# climate_control.net
KiCad netlist of a schematic drawn in EAGLE
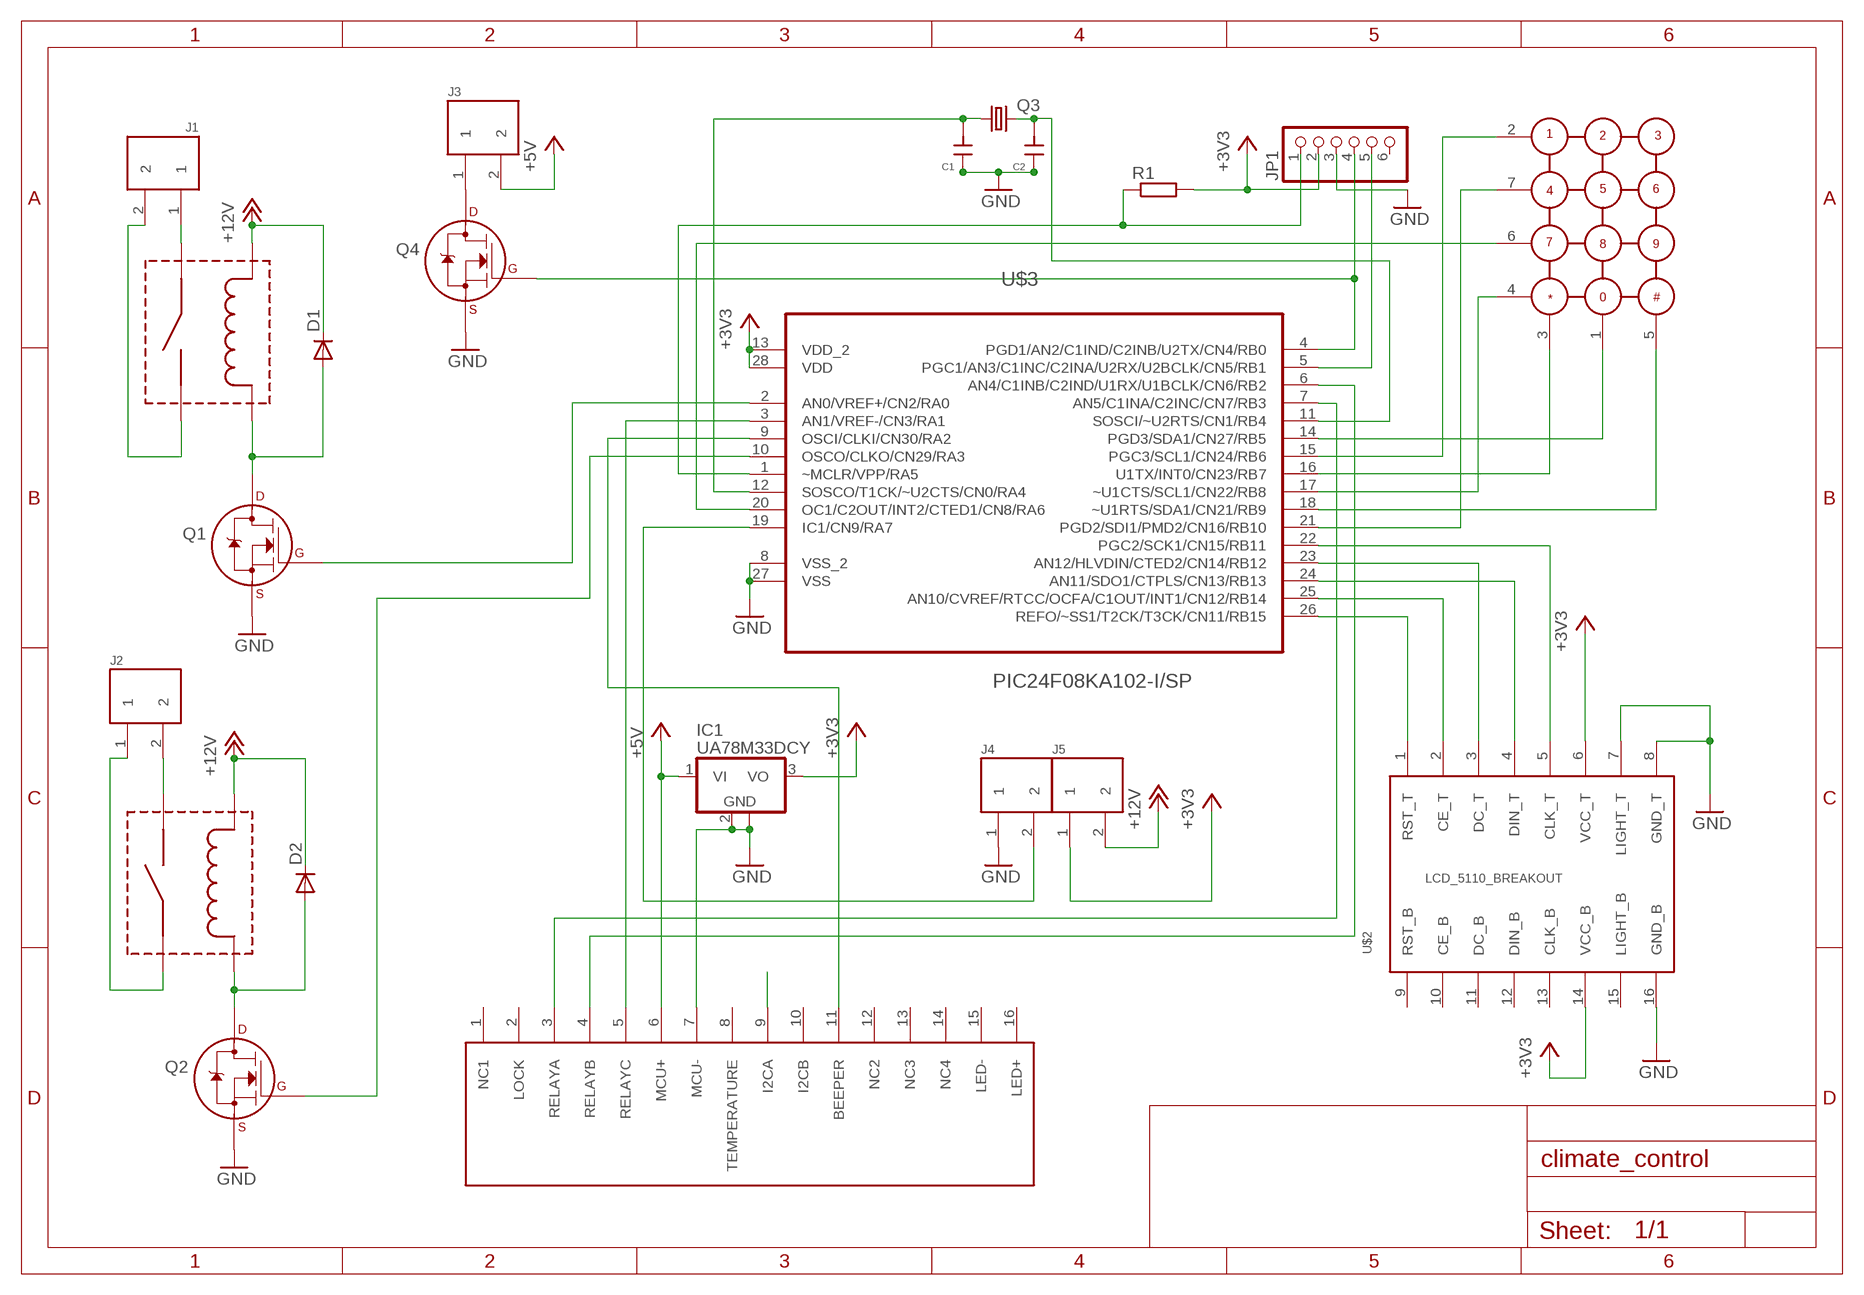
[diagram p0: schematic, sheet 1]

(export (version "E")
  (design (tool "Eeschema 10.0.6"))
  (components
    (comp (ref "C1")
      (value "DUALCAP")
      (footprint "eagle-import:DUALCAP")
      (libsource (lib "eagle-import") (part "DUALCAP"))
    )
    (comp (ref "C2")
      (value "DUALCAP")
      (footprint "eagle-import:DUALCAP")
      (libsource (lib "eagle-import") (part "DUALCAP"))
    )
    (comp (ref "D1")
      (value "DIODE-DO-214AC")
      (footprint "eagle-import:DO-214AC")
      (libsource (lib "eagle-import") (part "DIODE-DO-214AC"))
    )
    (comp (ref "D2")
      (value "DIODE-DO-214AC")
      (footprint "eagle-import:DO-214AC")
      (libsource (lib "eagle-import") (part "DIODE-DO-214AC"))
    )
    (comp (ref "IC1")
      (value "UA78M33DCY")
      (footprint "eagle-import:SOT223")
      (libsource (lib "eagle-import") (part "UA78MDCY33"))
    )
    (comp (ref "J1")
      (value "TERMINAL_PCB_508_X2")
      (footprint "eagle-import:TERMINAL_PCB_508_PITCH")
      (libsource (lib "eagle-import") (part "TERMINAL_PCB_508_X2"))
    )
    (comp (ref "J2")
      (value "TERMINAL_PCB_508_X2")
      (footprint "eagle-import:TERMINAL_PCB_508_PITCH")
      (libsource (lib "eagle-import") (part "TERMINAL_PCB_508_X2"))
    )
    (comp (ref "J3")
      (value "TERMINAL_PCB_508_X2")
      (footprint "eagle-import:TERMINAL_PCB_508_PITCH")
      (libsource (lib "eagle-import") (part "TERMINAL_PCB_508_X2"))
    )
    (comp (ref "J4")
      (value "TERMINAL_PCB_508_X2")
      (footprint "eagle-import:TERMINAL_PCB_508_PITCH")
      (libsource (lib "eagle-import") (part "TERMINAL_PCB_508_X2"))
    )
    (comp (ref "J5")
      (value "TERMINAL_PCB_508_X2")
      (footprint "eagle-import:TERMINAL_PCB_508_PITCH")
      (libsource (lib "eagle-import") (part "TERMINAL_PCB_508_X2"))
    )
    (comp (ref "JP1")
      (value "PINHD-1X6")
      (footprint "eagle-import:1X06")
      (libsource (lib "eagle-import") (part "PINHD-1X6"))
    )
    (comp (ref "Q1")
      (value "2N7000_TO92")
      (footprint "eagle-import:TO-92")
      (libsource (lib "eagle-import") (part "2N700_TO920"))
    )
    (comp (ref "Q2")
      (value "2N7000_TO92")
      (footprint "eagle-import:TO-92")
      (libsource (lib "eagle-import") (part "2N700_TO920"))
    )
    (comp (ref "Q3")
      (value "CRYSTALTC38H")
      (footprint "eagle-import:TC38H")
      (libsource (lib "eagle-import") (part "CRYSTALTC38H"))
    )
    (comp (ref "Q4")
      (value "2N7000_TO92")
      (footprint "eagle-import:TO-92")
      (libsource (lib "eagle-import") (part "2N700_TO920"))
    )
    (comp (ref "R1")
      (value "R-EU_0207/10")
      (footprint "eagle-import:0207_10")
      (libsource (lib "eagle-import") (part "R-EU_0207/10"))
    )
    (comp (ref "U$1")
      (value "KEYPAD12")
      (footprint "eagle-import:KEYPAD12")
      (libsource (lib "eagle-import") (part "KEYPAD12"))
    )
    (comp (ref "U$2")
      (value "LCD_5110_BREAKOUT")
      (footprint "eagle-import:LCD_5110_BREAKOUT")
      (libsource (lib "eagle-import") (part "LCD_5110_BREAKOUT"))
    )
    (comp (ref "U$3")
      (value "PIC24F08KA102-I/SP")
      (footprint "eagle-import:DIP254P762X533-28")
      (fields (field (name "MPN") "PIC24F08kA102-I/SP"))
      (libsource (lib "eagle-import") (part "PIC24F08KA102-I/SP"))
    )
    (comp (ref "U$4")
      (value "WILLHI_EDGE")
      (footprint "eagle-import:WILLHI_EDGE")
      (libsource (lib "eagle-import") (part "WILLHI_EDGE"))
    )
    (comp (ref "U$5")
      (value "RELAY_JZC-33F")
      (footprint "eagle-import:RELAY_JZC-33F")
      (libsource (lib "eagle-import") (part "RELAY_JZC-33F"))
    )
    (comp (ref "U$7")
      (value "RELAY_JZC-33F")
      (footprint "eagle-import:RELAY_JZC-33F")
      (libsource (lib "eagle-import") (part "RELAY_JZC-33F"))
    )
  )
  (nets
    (net (code "1") (name "+3V3") (class "Default")
      (node (ref "IC1") (pin "3") (pinfunction "VO_3") (pintype "passive"))
      (node (ref "J5") (pin "1") (pinfunction "1_1") (pintype "bidirectional"))
      (node (ref "JP1") (pin "2") (pinfunction "2_2") (pintype "passive"))
      (node (ref "R1") (pin "2") (pinfunction "2_2") (pintype "passive"))
      (node (ref "U$2") (pin "14") (pinfunction "VCC_B_14") (pintype "power_in"))
      (node (ref "U$2") (pin "6") (pinfunction "VCC_T_6") (pintype "power_in"))
      (node (ref "U$3") (pin "13") (pinfunction "VDD_2_13") (pintype "passive"))
      (node (ref "U$3") (pin "28") (pinfunction "VDD_28") (pintype "power_in"))
    )
    (net (code "2") (name "+5V") (class "Default")
      (node (ref "IC1") (pin "1") (pinfunction "VI_1") (pintype "input"))
      (node (ref "J3") (pin "2") (pinfunction "2_2") (pintype "bidirectional"))
      (node (ref "U$4") (pin "6") (pinfunction "MCU+_6") (pintype "bidirectional"))
    )
    (net (code "3") (name "+12V") (class "Default")
      (node (ref "D1") (pin "C") (pinfunction "C_C") (pintype "passive"))
      (node (ref "D2") (pin "C") (pinfunction "C_C") (pintype "passive"))
      (node (ref "J5") (pin "2") (pinfunction "2_2") (pintype "bidirectional"))
      (node (ref "U$5") (pin "COIL1") (pinfunction "COIL1_COIL1") (pintype "passive"))
      (node (ref "U$7") (pin "COIL2") (pinfunction "COIL2_COIL2") (pintype "passive"))
    )
    (net (code "4") (name "GND") (class "Default")
      (node (ref "C1") (pin "P$2") (pinfunction "P$2_P$2") (pintype "passive"))
      (node (ref "C1") (pin "P$3") (pinfunction "P$1_P$3") (pintype "passive"))
      (node (ref "C2") (pin "P$2") (pinfunction "P$2_P$2") (pintype "passive"))
      (node (ref "C2") (pin "P$3") (pinfunction "P$1_P$3") (pintype "passive"))
      (node (ref "IC1") (pin "2") (pinfunction "GND_2") (pintype "passive"))
      (node (ref "IC1") (pin "4") (pinfunction "GND_4") (pintype "passive"))
      (node (ref "J4") (pin "1") (pinfunction "1_1") (pintype "bidirectional"))
      (node (ref "JP1") (pin "3") (pinfunction "3_3") (pintype "passive"))
      (node (ref "Q1") (pin "1") (pinfunction "S_1") (pintype "bidirectional"))
      (node (ref "Q2") (pin "1") (pinfunction "S_1") (pintype "bidirectional"))
      (node (ref "Q4") (pin "1") (pinfunction "S_1") (pintype "bidirectional"))
      (node (ref "U$2") (pin "16") (pinfunction "GND_B_16") (pintype "power_in"))
      (node (ref "U$2") (pin "7") (pinfunction "LIGHT_T_7") (pintype "input"))
      (node (ref "U$2") (pin "8") (pinfunction "GND_T_8") (pintype "power_in"))
      (node (ref "U$3") (pin "27") (pinfunction "VSS_27") (pintype "passive"))
      (node (ref "U$3") (pin "8") (pinfunction "VSS_2_8") (pintype "passive"))
      (node (ref "U$4") (pin "7") (pinfunction "MCU-_7") (pintype "bidirectional"))
    )
    (net (code "5") (name "Net-(C1-P$3)") (class "Default")
      (node (ref "C1") (pin "P$1") (pinfunction "P$3_P$1") (pintype "passive"))
      (node (ref "Q3") (pin "1") (pinfunction "1_1") (pintype "passive"))
      (node (ref "U$3") (pin "12") (pinfunction "SOSCO/T1CK/~{U2CTS/CN0/RA4}_12") (pintype "bidirectional"))
    )
    (net (code "6") (name "Net-(C2-P$3)") (class "Default")
      (node (ref "C2") (pin "P$1") (pinfunction "P$3_P$1") (pintype "passive"))
      (node (ref "Q3") (pin "2") (pinfunction "2_2") (pintype "passive"))
      (node (ref "U$3") (pin "11") (pinfunction "SOSCI/~{U2RTS/CN1/RB4}_11") (pintype "bidirectional"))
    )
    (net (code "7") (name "Net-(J1-Pad1)") (class "Default")
      (node (ref "J1") (pin "1") (pinfunction "1_1") (pintype "bidirectional"))
      (node (ref "U$5") (pin "CONTACT1") (pinfunction "CONTACT1_CONTACT1") (pintype "passive"))
    )
    (net (code "8") (name "Net-(J1-Pad2)") (class "Default")
      (node (ref "J1") (pin "2") (pinfunction "2_2") (pintype "bidirectional"))
      (node (ref "U$5") (pin "CONTACT2") (pinfunction "CONTACT2_CONTACT2") (pintype "passive"))
    )
    (net (code "9") (name "Net-(J2-Pad1)") (class "Default")
      (node (ref "J2") (pin "1") (pinfunction "1_1") (pintype "bidirectional"))
      (node (ref "U$7") (pin "CONTACT1") (pinfunction "CONTACT1_CONTACT1") (pintype "passive"))
    )
    (net (code "10") (name "Net-(J2-Pad2)") (class "Default")
      (node (ref "J2") (pin "2") (pinfunction "2_2") (pintype "bidirectional"))
      (node (ref "U$7") (pin "CONTACT2") (pinfunction "CONTACT2_CONTACT2") (pintype "passive"))
    )
    (net (code "11") (name "Net-(Q1-D)") (class "Default")
      (node (ref "D1") (pin "A") (pinfunction "A_A") (pintype "passive"))
      (node (ref "Q1") (pin "3") (pinfunction "D_3") (pintype "bidirectional"))
      (node (ref "U$5") (pin "COIL2") (pinfunction "COIL2_COIL2") (pintype "passive"))
    )
    (net (code "12") (name "Net-(Q1-G)") (class "Default")
      (node (ref "Q1") (pin "2") (pinfunction "G_2") (pintype "tri_state"))
      (node (ref "U$3") (pin "2") (pinfunction "AN0/VREF+/CN2/RA0_2") (pintype "bidirectional"))
    )
    (net (code "13") (name "Net-(Q2-D)") (class "Default")
      (node (ref "D2") (pin "A") (pinfunction "A_A") (pintype "passive"))
      (node (ref "Q2") (pin "3") (pinfunction "D_3") (pintype "bidirectional"))
      (node (ref "U$7") (pin "COIL1") (pinfunction "COIL1_COIL1") (pintype "passive"))
    )
    (net (code "14") (name "Net-(Q2-G)") (class "Default")
      (node (ref "Q2") (pin "2") (pinfunction "G_2") (pintype "tri_state"))
      (node (ref "U$3") (pin "10") (pinfunction "OSCO/CLKO/CN29/RA3_10") (pintype "bidirectional"))
    )
    (net (code "15") (name "Net-(Q4-D)") (class "Default")
      (node (ref "J3") (pin "1") (pinfunction "1_1") (pintype "bidirectional"))
      (node (ref "Q4") (pin "3") (pinfunction "D_3") (pintype "bidirectional"))
    )
    (net (code "16") (name "Net-(Q4-G)") (class "Default")
      (node (ref "JP1") (pin "4") (pinfunction "4_4") (pintype "passive"))
      (node (ref "Q4") (pin "2") (pinfunction "G_2") (pintype "tri_state"))
      (node (ref "U$3") (pin "4") (pinfunction "PGD1/AN2/C1IND/C2INB/U2TX/CN4/RB0_4") (pintype "bidirectional"))
    )
    (net (code "17") (name "Net-(U$1-*0#)") (class "Default")
      (node (ref "U$1") (pin "4") (pinfunction "*0#_4") (pintype "bidirectional"))
      (node (ref "U$3") (pin "17") (pinfunction "~{U1CTS/SCL1/CN22/RB8}_17") (pintype "bidirectional"))
    )
    (net (code "18") (name "Net-(U$1-123)") (class "Default")
      (node (ref "U$1") (pin "2") (pinfunction "123_2") (pintype "bidirectional"))
      (node (ref "U$3") (pin "15") (pinfunction "PGC3/SCL1/CN24/RB6_15") (pintype "bidirectional"))
    )
    (net (code "19") (name "Net-(U$1-147*)") (class "Default")
      (node (ref "U$1") (pin "3") (pinfunction "147*_3") (pintype "bidirectional"))
      (node (ref "U$3") (pin "16") (pinfunction "U1TX/INT0/CN23/RB7_16") (pintype "bidirectional"))
    )
    (net (code "20") (name "Net-(U$1-369#)") (class "Default")
      (node (ref "U$1") (pin "5") (pinfunction "369#_5") (pintype "bidirectional"))
      (node (ref "U$3") (pin "18") (pinfunction "~{U1RTS/SDA1/CN21/RB9}_18") (pintype "bidirectional"))
    )
    (net (code "21") (name "Net-(U$1-456)") (class "Default")
      (node (ref "U$1") (pin "7") (pinfunction "456_7") (pintype "bidirectional"))
      (node (ref "U$3") (pin "21") (pinfunction "PGD2/SDI1/PMD2/CN16/RB10_21") (pintype "bidirectional"))
    )
    (net (code "22") (name "Net-(U$1-789)") (class "Default")
      (node (ref "U$1") (pin "6") (pinfunction "789_6") (pintype "bidirectional"))
      (node (ref "U$3") (pin "20") (pinfunction "OC1/C2OUT/INT2/CTED1/CN8/RA6_20") (pintype "bidirectional"))
    )
    (net (code "23") (name "Net-(U$1-2580)") (class "Default")
      (node (ref "U$1") (pin "1") (pinfunction "2580_1") (pintype "bidirectional"))
      (node (ref "U$3") (pin "14") (pinfunction "PGD3/SDA1/CN27/RB5_14") (pintype "bidirectional"))
    )
    (net (code "24") (name "Net-(U$2-CE_T)") (class "Default")
      (node (ref "U$2") (pin "2") (pinfunction "CE_T_2") (pintype "input"))
      (node (ref "U$3") (pin "25") (pinfunction "AN10/CVREF/RTCC/OCFA/C1OUT/INT1/CN12/RB14_25") (pintype "bidirectional"))
    )
    (net (code "25") (name "Net-(U$2-CLK_T)") (class "Default")
      (node (ref "U$2") (pin "5") (pinfunction "CLK_T_5") (pintype "input"))
      (node (ref "U$3") (pin "22") (pinfunction "PGC2/SCK1/CN15/RB11_22") (pintype "bidirectional"))
    )
    (net (code "26") (name "Net-(U$2-DC_T)") (class "Default")
      (node (ref "U$2") (pin "3") (pinfunction "DC_T_3") (pintype "input"))
      (node (ref "U$3") (pin "23") (pinfunction "AN12/HLVDIN/CTED2/CN14/RB12_23") (pintype "bidirectional"))
    )
    (net (code "27") (name "Net-(U$2-DIN_T)") (class "Default")
      (node (ref "U$2") (pin "4") (pinfunction "DIN_T_4") (pintype "input"))
      (node (ref "U$3") (pin "24") (pinfunction "AN11/SDO1/CTPLS/CN13/RB13_24") (pintype "bidirectional"))
    )
    (net (code "28") (name "Net-(U$2-RST_T)") (class "Default")
      (node (ref "U$2") (pin "1") (pinfunction "RST_T_1") (pintype "input"))
      (node (ref "U$3") (pin "26") (pinfunction "REFO/~{SS1/T2CK/T3CK/CN11/RB15}_26") (pintype "bidirectional"))
    )
    (net (code "29") (name "Net-(U$3-AN1{slash}VREF-{slash}CN3{slash}RA1)") (class "Default")
      (node (ref "U$3") (pin "3") (pinfunction "AN1/VREF-/CN3/RA1_3") (pintype "bidirectional"))
      (node (ref "U$4") (pin "5") (pinfunction "RELAYC_5") (pintype "bidirectional"))
    )
    (net (code "30") (name "Net-(U$3-AN4{slash}C1INB{slash}C2IND{slash}U1RX{slash}U1BCLK{slash}CN6{slash}RB2)") (class "Default")
      (node (ref "U$3") (pin "6") (pinfunction "AN4/C1INB/C2IND/U1RX/U1BCLK/CN6/RB2_6") (pintype "bidirectional"))
      (node (ref "U$4") (pin "4") (pinfunction "RELAYB_4") (pintype "bidirectional"))
    )
    (net (code "31") (name "Net-(U$3-AN5{slash}C1INA{slash}C2INC{slash}CN7{slash}RB3)") (class "Default")
      (node (ref "U$3") (pin "7") (pinfunction "AN5/C1INA/C2INC/CN7/RB3_7") (pintype "bidirectional"))
      (node (ref "U$4") (pin "3") (pinfunction "RELAYA_3") (pintype "bidirectional"))
    )
    (net (code "32") (name "Net-(U$3-IC1{slash}CN9{slash}RA7)") (class "Default")
      (node (ref "J4") (pin "2") (pinfunction "2_2") (pintype "bidirectional"))
      (node (ref "U$3") (pin "19") (pinfunction "IC1/CN9/RA7_19") (pintype "bidirectional"))
    )
    (net (code "33") (name "Net-(U$3-OSCI{slash}CLKI{slash}CN30{slash}RA2)") (class "Default")
      (node (ref "U$3") (pin "9") (pinfunction "OSCI/CLKI/CN30/RA2_9") (pintype "bidirectional"))
      (node (ref "U$4") (pin "11") (pinfunction "BEEPER_11") (pintype "bidirectional"))
    )
    (net (code "34") (name "Net-(U$3-PGC1{slash}AN3{slash}C1INC{slash}C2INA{slash}U2RX{slash}U2BCLK{slash}CN5{slash}RB1)") (class "Default")
      (node (ref "JP1") (pin "5") (pinfunction "5_5") (pintype "passive"))
      (node (ref "U$3") (pin "5") (pinfunction "PGC1/AN3/C1INC/C2INA/U2RX/U2BCLK/CN5/RB1_5") (pintype "bidirectional"))
    )
    (net (code "35") (name "Net-(U$3-~{MCLR{slash}VPP{slash}RA5})") (class "Default")
      (node (ref "JP1") (pin "1") (pinfunction "1_1") (pintype "passive"))
      (node (ref "R1") (pin "1") (pinfunction "1_1") (pintype "passive"))
      (node (ref "U$3") (pin "1") (pinfunction "~{MCLR/VPP/RA5}_1") (pintype "bidirectional"))
    )
    (net (code "36") (name "unconnected-(JP1-Pad6)") (class "Default")
      (node (ref "JP1") (pin "6") (pinfunction "6_6") (pintype "passive"))
    )
    (net (code "37") (name "unconnected-(U$2-CE_B-Pad10)") (class "Default")
      (node (ref "U$2") (pin "10") (pinfunction "CE_B_10") (pintype "input"))
    )
    (net (code "38") (name "unconnected-(U$2-CLK_B-Pad13)") (class "Default")
      (node (ref "U$2") (pin "13") (pinfunction "CLK_B_13") (pintype "input"))
    )
    (net (code "39") (name "unconnected-(U$2-DC_B-Pad11)") (class "Default")
      (node (ref "U$2") (pin "11") (pinfunction "DC_B_11") (pintype "input"))
    )
    (net (code "40") (name "unconnected-(U$2-DIN_B-Pad12)") (class "Default")
      (node (ref "U$2") (pin "12") (pinfunction "DIN_B_12") (pintype "input"))
    )
    (net (code "41") (name "unconnected-(U$2-LIGHT_B-Pad15)") (class "Default")
      (node (ref "U$2") (pin "15") (pinfunction "LIGHT_B_15") (pintype "input"))
    )
    (net (code "42") (name "unconnected-(U$2-RST_B-Pad9)") (class "Default")
      (node (ref "U$2") (pin "9") (pinfunction "RST_B_9") (pintype "input"))
    )
    (net (code "43") (name "unconnected-(U$4-I2CA-Pad9)") (class "Default")
      (node (ref "U$4") (pin "9") (pinfunction "I2CA_9") (pintype "bidirectional"))
    )
    (net (code "44") (name "unconnected-(U$4-I2CB-Pad10)") (class "Default")
      (node (ref "U$4") (pin "10") (pinfunction "I2CB_10") (pintype "bidirectional"))
    )
    (net (code "45") (name "unconnected-(U$4-LED+-Pad16)") (class "Default")
      (node (ref "U$4") (pin "16") (pinfunction "LED+_16") (pintype "bidirectional"))
    )
    (net (code "46") (name "unconnected-(U$4-LED--Pad15)") (class "Default")
      (node (ref "U$4") (pin "15") (pinfunction "LED-_15") (pintype "bidirectional"))
    )
    (net (code "47") (name "unconnected-(U$4-LOCK-Pad2)") (class "Default")
      (node (ref "U$4") (pin "2") (pinfunction "LOCK_2") (pintype "bidirectional"))
    )
    (net (code "48") (name "unconnected-(U$4-NC1-Pad1)") (class "Default")
      (node (ref "U$4") (pin "1") (pinfunction "NC1_1") (pintype "bidirectional"))
    )
    (net (code "49") (name "unconnected-(U$4-NC2-Pad12)") (class "Default")
      (node (ref "U$4") (pin "12") (pinfunction "NC2_12") (pintype "bidirectional"))
    )
    (net (code "50") (name "unconnected-(U$4-NC3-Pad13)") (class "Default")
      (node (ref "U$4") (pin "13") (pinfunction "NC3_13") (pintype "bidirectional"))
    )
    (net (code "51") (name "unconnected-(U$4-NC4-Pad14)") (class "Default")
      (node (ref "U$4") (pin "14") (pinfunction "NC4_14") (pintype "bidirectional"))
    )
    (net (code "52") (name "unconnected-(U$4-TEMPERATURE-Pad8)") (class "Default")
      (node (ref "U$4") (pin "8") (pinfunction "TEMPERATURE_8") (pintype "bidirectional"))
    )
  )
)
